# battery_charger.net
KiCad netlist of a schematic drawn in Altium Designer
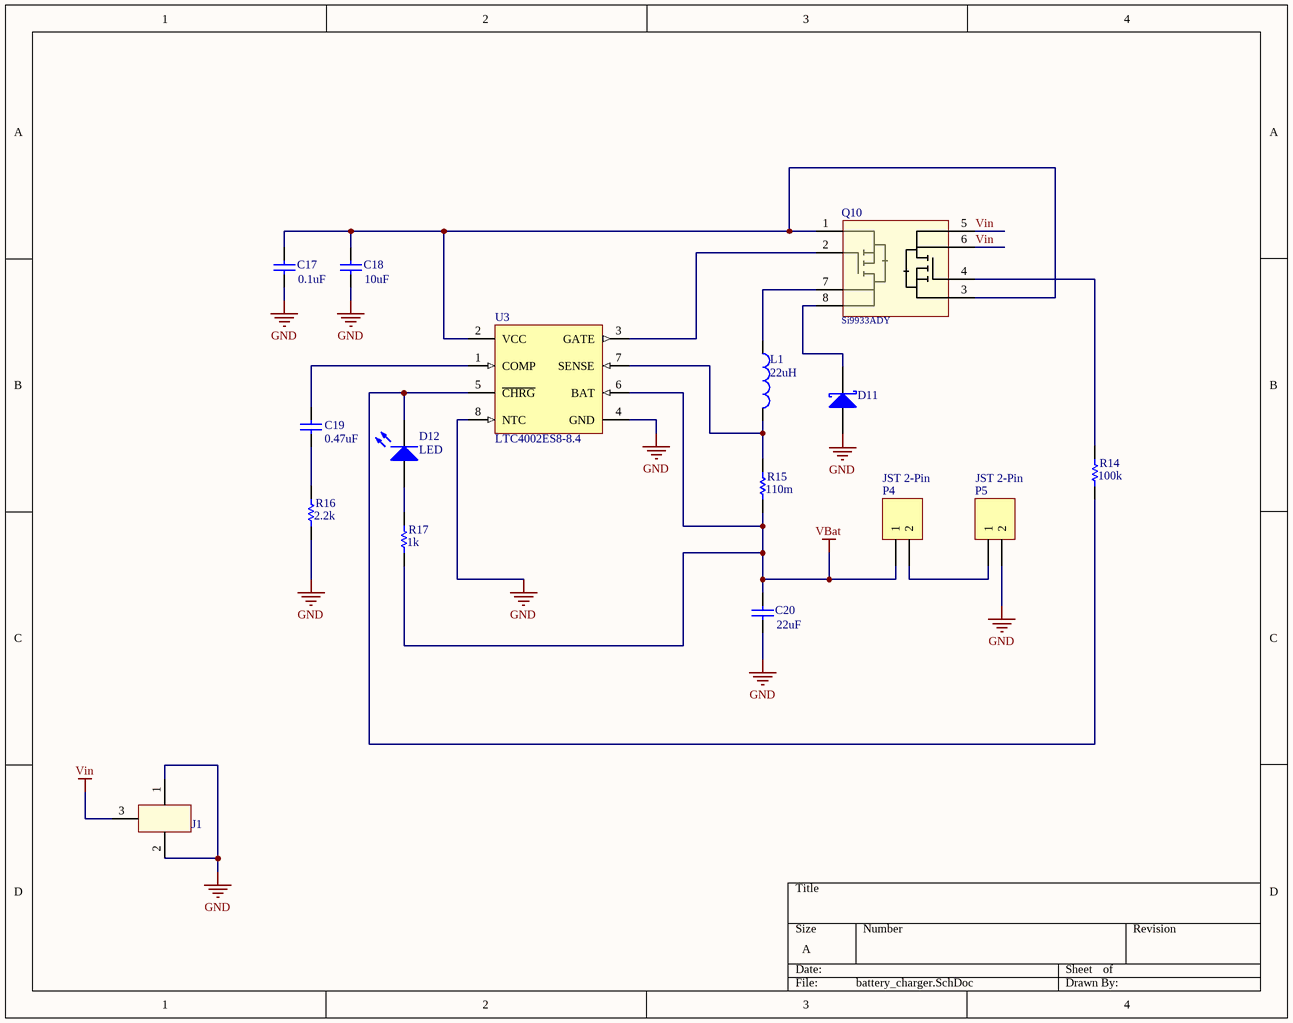
[diagram p0: battery_charger.SchDoc]

(export (version "E")
  (design (tool "Eeschema 10.0.6"))
  (components
    (comp (ref "C17")
      (value "0.1uF")
      (footprint "1608[0603]")
      (description "Capacitor (Semiconductor SIM Model)")
      (fields (field (name "Comment") "Cap Semi") (field (name "PUBLISHER") "Altium Limited"))
      (libsource (lib "Miscellaneous Devices") (part "Cap Semi"))
    )
    (comp (ref "C18")
      (value "10uF")
      (footprint "C1210")
      (description "Capacitor (Semiconductor SIM Model)")
      (fields (field (name "Comment") "Cap Semi") (field (name "PUBLISHER") "Altium Limited"))
      (libsource (lib "Miscellaneous Devices") (part "Cap Semi"))
    )
    (comp (ref "C19")
      (value "0.47uF")
      (footprint "1608[0603]")
      (description "Capacitor (Semiconductor SIM Model)")
      (fields (field (name "Comment") "Cap Semi") (field (name "PUBLISHER") "Altium Limited"))
      (libsource (lib "Miscellaneous Devices") (part "Cap Semi"))
    )
    (comp (ref "C20")
      (value "22uF")
      (footprint "C1210")
      (description "Capacitor (Semiconductor SIM Model)")
      (fields (field (name "Comment") "Cap Semi") (field (name "PUBLISHER") "Altium Limited"))
      (libsource (lib "Miscellaneous Devices") (part "Cap Semi"))
    )
    (comp (ref "D11")
      (value "D Schottky")
      (footprint "SMB")
      (description "Schottky Diode")
      (fields (field (name "PUBLISHER") "Altium Limited"))
      (libsource (lib "Miscellaneous Devices") (part "D Schottky"))
    )
    (comp (ref "D12")
      (value "LED")
      (footprint "0603")
      (fields
        (field (name "VENDOR PART NUMBER") "751-1203-ND")
        (field (name "MANUFACTURER") "Vishay")
        (field (name "MANUFACTURER PART NUMBER") "TSAL6100")
        (field (name "PUBLISHER") "Anthony Merlino")
      )
      (libsource (lib "passives") (part "LED"))
    )
    (comp (ref "J1")
      (value "DC Barrel Jack")
      (footprint "DC Barrel Jack")
      (description "DC Barrel Jack, Fits 5mm DC Wall Adapter")
      (libsource (lib "connectors") (part "DC Barrel Jack"))
    )
    (comp (ref "L1")
      (value "22uH")
      (footprint "INDC6060X49N")
      (description "Inductor")
      (fields (field (name "PUBLISHER") "Altium Limited"))
      (libsource (lib "passives") (part "Inductor"))
    )
    (comp (ref "P4")
      (value "JST 2-Pin")
      (footprint "JST Connector 2-pin")
      (description "Header, 2-Pin")
      (fields (field (name "PUBLISHER") "Altium Limited"))
      (libsource (lib "connectors") (part "JST Connector 2-Pin"))
    )
    (comp (ref "P5")
      (value "JST 2-Pin")
      (footprint "JST Connector 2-pin")
      (description "Header, 2-Pin")
      (fields (field (name "PUBLISHER") "Altium Limited"))
      (libsource (lib "connectors") (part "JST Connector 2-Pin"))
    )
    (comp (ref "Q10")
      (value "Dual P-Channel")
      (footprint "SM_IC:SOIC-8")
      (description "Dual P-Channel 20-V (D-S) MOSFET")
      (fields (field (name "MANUFACTURER PART N.O.") "Si9933ADY"))
      (libsource (lib "transistors") (part "Si9933ADY"))
    )
    (comp (ref "R14")
      (value "100k")
      (footprint "0603")
      (description "Resistor")
      (fields (field (name "PUBLISHER") "Altium Limited"))
      (libsource (lib "passives") (part "Resistor"))
    )
    (comp (ref "R15")
      (value "110m")
      (footprint "0603")
      (description "Resistor")
      (fields (field (name "PUBLISHER") "Altium Limited"))
      (libsource (lib "passives") (part "Resistor"))
    )
    (comp (ref "R16")
      (value "2.2k")
      (footprint "0603")
      (description "Resistor")
      (fields (field (name "PUBLISHER") "Altium Limited"))
      (libsource (lib "passives") (part "Resistor"))
    )
    (comp (ref "R17")
      (value "1k")
      (footprint "0603")
      (description "Resistor")
      (fields (field (name "PUBLISHER") "Altium Limited"))
      (libsource (lib "passives") (part "Resistor"))
    )
    (comp (ref "U3")
      (value "LTC4002ES8-8.4")
      (footprint "LT-S8-8_N")
      (description "Standalone Li-Ion Switch Mode Battery Charger, 8.9 to 22 V Vin, 8-pin SOIC (S8-8), -40 to 85 degC")
      (fields (field (name "MANUFACTURER") "Linear Technology"))
      (libsource (lib "Linear Technology Power Management Battery Management") (part "LTC4002ES8-8.4"))
    )
  )
  (nets
    (net (code "1") (name "GND") (class "Default")
      (node (ref "C17") (pin "1") (pinfunction "1_1") (pintype "passive"))
      (node (ref "C18") (pin "1") (pinfunction "1_1") (pintype "passive"))
      (node (ref "C20") (pin "1") (pinfunction "1_1") (pintype "passive"))
      (node (ref "D11") (pin "1") (pinfunction "A_1") (pintype "passive"))
      (node (ref "J1") (pin "1") (pinfunction "Casing_1") (pintype "passive"))
      (node (ref "J1") (pin "2") (pinfunction "Casing_2") (pintype "passive"))
      (node (ref "P5") (pin "2") (pinfunction "2_2") (pintype "passive"))
      (node (ref "R16") (pin "1") (pinfunction "1_1") (pintype "passive"))
      (node (ref "U3") (pin "4") (pinfunction "GND_4") (pintype "power_in"))
      (node (ref "U3") (pin "8") (pinfunction "NTC_8") (pintype "input"))
    )
    (net (code "2") (name "Net-(C19-Pad1)") (class "Default")
      (node (ref "C19") (pin "1") (pinfunction "1_1") (pintype "passive"))
      (node (ref "R16") (pin "2") (pinfunction "2_2") (pintype "passive"))
    )
    (net (code "3") (name "Net-(D11-K)") (class "Default")
      (node (ref "D11") (pin "2") (pinfunction "K_2") (pintype "passive"))
      (node (ref "Q10") (pin "8") (pinfunction "D1_8") (pintype "passive"))
    )
    (net (code "4") (name "Net-(D12-A)") (class "Default")
      (node (ref "D12") (pin "1") (pinfunction "A_1") (pintype "passive"))
      (node (ref "R17") (pin "2") (pinfunction "2_2") (pintype "passive"))
    )
    (net (code "5") (name "Net-(D12-K)") (class "Default")
      (node (ref "D12") (pin "2") (pinfunction "K_2") (pintype "passive"))
      (node (ref "R14") (pin "1") (pinfunction "1_1") (pintype "passive"))
      (node (ref "U3") (pin "5") (pinfunction "~{CHRG}_5") (pintype "tri_state"))
    )
    (net (code "6") (name "Net-(L1-Pad1)") (class "Default")
      (node (ref "L1") (pin "1") (pinfunction "1_1") (pintype "passive"))
      (node (ref "Q10") (pin "7") (pinfunction "D1_7") (pintype "passive"))
    )
    (net (code "7") (name "Net-(P4-Pad2)") (class "Default")
      (node (ref "P4") (pin "2") (pinfunction "2_2") (pintype "passive"))
      (node (ref "P5") (pin "1") (pinfunction "1_1") (pintype "passive"))
    )
    (net (code "8") (name "Net-(Q10-G1)") (class "Default")
      (node (ref "Q10") (pin "2") (pinfunction "G1_2") (pintype "passive"))
      (node (ref "U3") (pin "3") (pinfunction "GATE_3") (pintype "output"))
    )
    (net (code "9") (name "Net-(Q10-G2)") (class "Default")
      (node (ref "Q10") (pin "4") (pinfunction "G2_4") (pintype "passive"))
      (node (ref "R14") (pin "2") (pinfunction "2_2") (pintype "passive"))
    )
    (net (code "10") (name "Net-(Q10-S1)") (class "Default")
      (node (ref "C17") (pin "2") (pinfunction "2_2") (pintype "passive"))
      (node (ref "C18") (pin "2") (pinfunction "2_2") (pintype "passive"))
      (node (ref "Q10") (pin "1") (pinfunction "S1_1") (pintype "passive"))
      (node (ref "Q10") (pin "3") (pinfunction "S2_3") (pintype "passive"))
      (node (ref "U3") (pin "2") (pinfunction "VCC_2") (pintype "power_in"))
    )
    (net (code "11") (name "Net-(U3-COMP)") (class "Default")
      (node (ref "C19") (pin "2") (pinfunction "2_2") (pintype "passive"))
      (node (ref "U3") (pin "1") (pinfunction "COMP_1") (pintype "input"))
    )
    (net (code "12") (name "Net-(U3-SENSE)") (class "Default")
      (node (ref "L1") (pin "2") (pinfunction "2_2") (pintype "passive"))
      (node (ref "R15") (pin "2") (pinfunction "2_2") (pintype "passive"))
      (node (ref "U3") (pin "7") (pinfunction "SENSE_7") (pintype "input"))
    )
    (net (code "13") (name "VBat") (class "Default")
      (node (ref "C20") (pin "2") (pinfunction "2_2") (pintype "passive"))
      (node (ref "P4") (pin "1") (pinfunction "1_1") (pintype "passive"))
      (node (ref "R15") (pin "1") (pinfunction "1_1") (pintype "passive"))
      (node (ref "R17") (pin "1") (pinfunction "1_1") (pintype "passive"))
      (node (ref "U3") (pin "6") (pinfunction "BAT_6") (pintype "input"))
    )
    (net (code "14") (name "Vin") (class "Default")
      (node (ref "J1") (pin "3") (pinfunction "Center_3") (pintype "passive"))
      (node (ref "Q10") (pin "5") (pinfunction "D2_5") (pintype "passive"))
      (node (ref "Q10") (pin "6") (pinfunction "D2_6") (pintype "passive"))
    )
  )
)
